# Connectors.net
KiCad netlist of a schematic drawn in Altium Designer
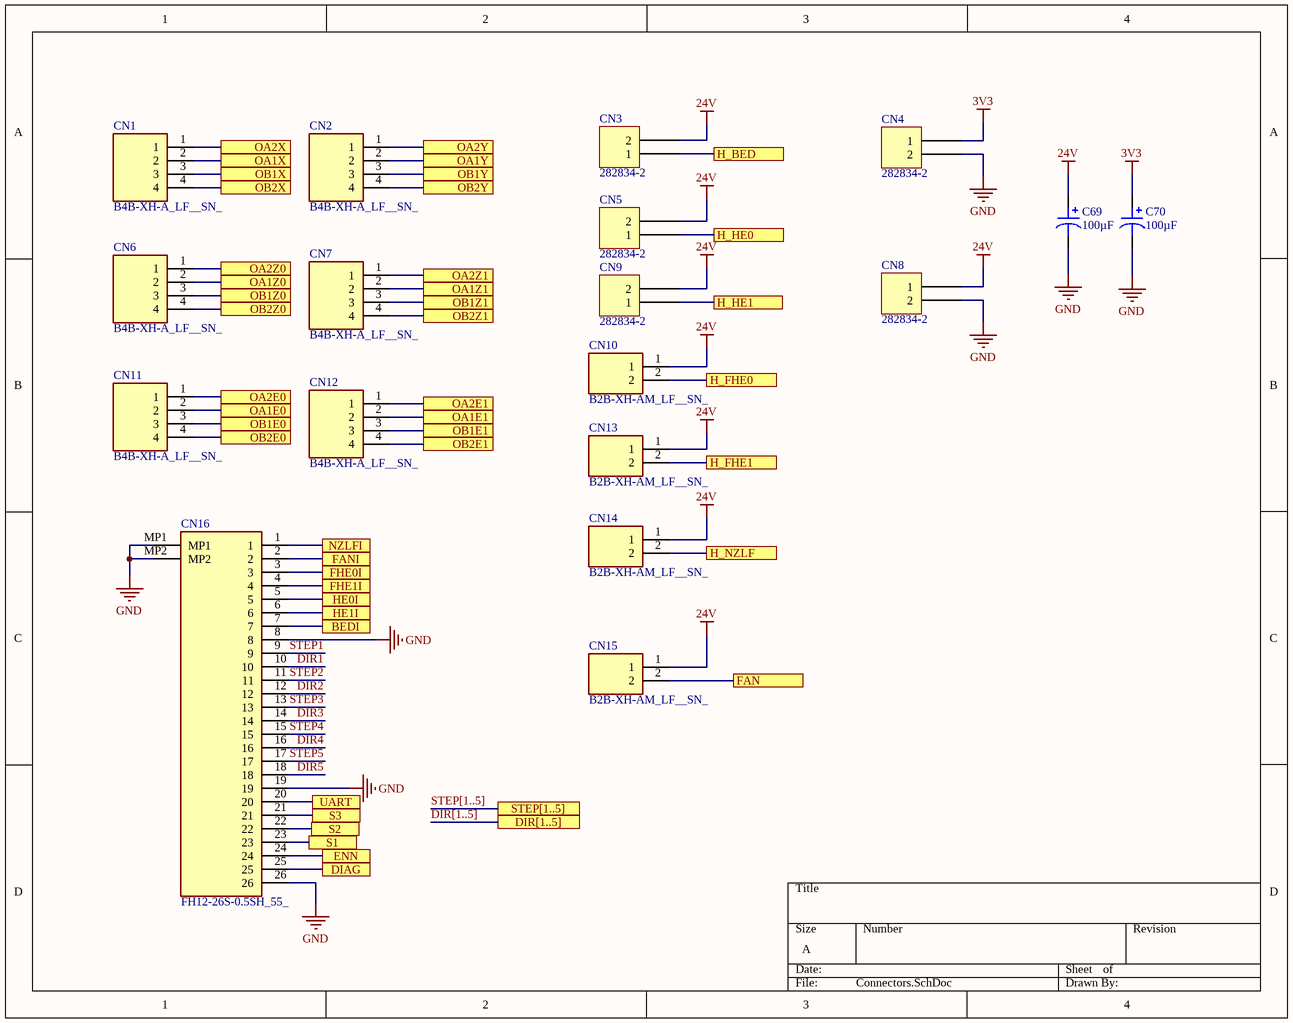
[diagram p0: Connectors.SchDoc]

(export (version "E")
  (design (tool "Eeschema 10.0.6"))
  (components
    (comp (ref "C69")
      (value "100µF")
      (footprint "CAP ALSMD POLY 5.3MM H6.0MM")
      (description "CAP ALUM POLY 100UF 20% 6.3V SMD")
      (fields
        (field (name "PART NUMBER") "6SVPC100M")
        (field (name "MANUFACTURER") "Panasonic Electronic Components")
      )
      (libsource (lib "Celestial Altium Library - altium_library") (part "Polarised Capacitor"))
    )
    (comp (ref "C70")
      (value "100µF")
      (footprint "CAP ALSMD POLY 5.3MM H6.0MM")
      (description "CAP ALUM POLY 100UF 20% 6.3V SMD")
      (fields
        (field (name "PART NUMBER") "6SVPC100M")
        (field (name "MANUFACTURER") "Panasonic Electronic Components")
      )
      (libsource (lib "Celestial Altium Library - altium_library") (part "Polarised Capacitor"))
    )
    (comp (ref "CN1")
      (value "B4B-XH-A_LF__SN_")
      (footprint "SamacSys:B4BXHALFSN")
      (description "Connector")
      (fields (field (name "MANUFACTURER_PART_NUMBER") "B4B-XH-A(LF)(SN)"))
      (libsource (lib "*") (part "B4B-XH-A_LF__SN_"))
    )
    (comp (ref "CN2")
      (value "B4B-XH-A_LF__SN_")
      (footprint "SamacSys:B4BXHALFSN")
      (description "Connector")
      (fields (field (name "MANUFACTURER_PART_NUMBER") "B4B-XH-A(LF)(SN)"))
      (libsource (lib "*") (part "B4B-XH-A_LF__SN_"))
    )
    (comp (ref "CN3")
      (value "282834-2")
      (footprint "TE 282834-2")
      (description "TERM BLK 2P SIDE ENT 2.54MM PCB")
      (fields (field (name "MANUFACTURER") "TE Connectivity AMP Connectors") (field (name "VOLTAGE") "150V"))
      (libsource (lib "Celestial Altium Library - altium_library") (part "2 Pin"))
    )
    (comp (ref "CN4")
      (value "282834-2")
      (footprint "TE 282834-2")
      (description "TERM BLK 2P SIDE ENT 2.54MM PCB")
      (fields (field (name "MANUFACTURER") "TE Connectivity AMP Connectors") (field (name "VOLTAGE") "150V"))
      (libsource (lib "") (part "2 Pin_1"))
    )
    (comp (ref "CN5")
      (value "282834-2")
      (footprint "TE 282834-2")
      (description "TERM BLK 2P SIDE ENT 2.54MM PCB")
      (fields (field (name "MANUFACTURER") "TE Connectivity AMP Connectors") (field (name "VOLTAGE") "150V"))
      (libsource (lib "Celestial Altium Library - altium_library") (part "2 Pin"))
    )
    (comp (ref "CN6")
      (value "B4B-XH-A_LF__SN_")
      (footprint "SamacSys:B4BXHALFSN")
      (description "Connector")
      (fields (field (name "MANUFACTURER_PART_NUMBER") "B4B-XH-A(LF)(SN)"))
      (libsource (lib "*") (part "B4B-XH-A_LF__SN_"))
    )
    (comp (ref "CN7")
      (value "B4B-XH-A_LF__SN_")
      (footprint "SamacSys:B4BXHALFSN")
      (description "Connector")
      (fields (field (name "MANUFACTURER_PART_NUMBER") "B4B-XH-A(LF)(SN)"))
      (libsource (lib "*") (part "B4B-XH-A_LF__SN_"))
    )
    (comp (ref "CN8")
      (value "282834-2")
      (footprint "TE 282834-2")
      (description "TERM BLK 2P SIDE ENT 2.54MM PCB")
      (fields (field (name "MANUFACTURER") "TE Connectivity AMP Connectors") (field (name "VOLTAGE") "150V"))
      (libsource (lib "") (part "2 Pin_1"))
    )
    (comp (ref "CN9")
      (value "282834-2")
      (footprint "TE 282834-2")
      (description "TERM BLK 2P SIDE ENT 2.54MM PCB")
      (fields (field (name "MANUFACTURER") "TE Connectivity AMP Connectors") (field (name "VOLTAGE") "150V"))
      (libsource (lib "Celestial Altium Library - altium_library") (part "2 Pin"))
    )
    (comp (ref "CN10")
      (value "B2B-XH-AM_LF__SN_")
      (footprint "SamacSys:B2BXHAMLFSN")
      (description "Connector")
      (fields (field (name "MANUFACTURER_PART_NUMBER") "B2B-XH-AM(LF)(SN)"))
      (libsource (lib "*") (part "B2B-XH-AM_LF__SN_"))
    )
    (comp (ref "CN11")
      (value "B4B-XH-A_LF__SN_")
      (footprint "SamacSys:B4BXHALFSN")
      (description "Connector")
      (fields (field (name "MANUFACTURER_PART_NUMBER") "B4B-XH-A(LF)(SN)"))
      (libsource (lib "*") (part "B4B-XH-A_LF__SN_"))
    )
    (comp (ref "CN12")
      (value "B4B-XH-A_LF__SN_")
      (footprint "SamacSys:B4BXHALFSN")
      (description "Connector")
      (fields (field (name "MANUFACTURER_PART_NUMBER") "B4B-XH-A(LF)(SN)"))
      (libsource (lib "*") (part "B4B-XH-A_LF__SN_"))
    )
    (comp (ref "CN13")
      (value "B2B-XH-AM_LF__SN_")
      (footprint "SamacSys:B2BXHAMLFSN")
      (description "Connector")
      (fields (field (name "MANUFACTURER_PART_NUMBER") "B2B-XH-AM(LF)(SN)"))
      (libsource (lib "*") (part "B2B-XH-AM_LF__SN_"))
    )
    (comp (ref "CN14")
      (value "B2B-XH-AM_LF__SN_")
      (footprint "SamacSys:B2BXHAMLFSN")
      (description "Connector")
      (fields (field (name "MANUFACTURER_PART_NUMBER") "B2B-XH-AM(LF)(SN)"))
      (libsource (lib "*") (part "B2B-XH-AM_LF__SN_"))
    )
    (comp (ref "CN15")
      (value "B2B-XH-AM_LF__SN_")
      (footprint "SamacSys:B2BXHAMLFSN")
      (description "Connector")
      (fields (field (name "MANUFACTURER_PART_NUMBER") "B2B-XH-AM(LF)(SN)"))
      (libsource (lib "*") (part "B2B-XH-AM_LF__SN_"))
    )
    (comp (ref "CN16")
      (value "FH12-26S-0.5SH_55_")
      (footprint "SamacSys:FH1226S05SH55")
      (description "Connector")
      (fields
        (field (name "MANUFACTURER_PART_NUMBER") "FH12-26S-0.5SH(55)")
        (field (name "MOUSER PART NUMBER") "798-FH12-26S-0.5SH55")
      )
      (libsource (lib "SamacSys") (part "FH12-26S-0.5SH_55_"))
    )
  )
  (nets
    (net (code "1") (name "/BEDI") (class "Default")
      (node (ref "CN16") (pin "7") (pinfunction "7_7") (pintype "passive"))
    )
    (net (code "2") (name "/DIAG") (class "Default")
      (node (ref "CN16") (pin "25") (pinfunction "25_25") (pintype "passive"))
    )
    (net (code "3") (name "/DIR1") (class "Default")
      (node (ref "CN16") (pin "10") (pinfunction "10_10") (pintype "passive"))
    )
    (net (code "4") (name "/DIR2") (class "Default")
      (node (ref "CN16") (pin "12") (pinfunction "12_12") (pintype "passive"))
    )
    (net (code "5") (name "/DIR3") (class "Default")
      (node (ref "CN16") (pin "14") (pinfunction "14_14") (pintype "passive"))
    )
    (net (code "6") (name "/DIR4") (class "Default")
      (node (ref "CN16") (pin "16") (pinfunction "16_16") (pintype "passive"))
    )
    (net (code "7") (name "/DIR5") (class "Default")
      (node (ref "CN16") (pin "18") (pinfunction "18_18") (pintype "passive"))
    )
    (net (code "9") (name "/ENN") (class "Default")
      (node (ref "CN16") (pin "24") (pinfunction "24_24") (pintype "passive"))
    )
    (net (code "10") (name "/FAN") (class "Default")
      (node (ref "CN15") (pin "2") (pinfunction "2_2") (pintype "passive"))
    )
    (net (code "11") (name "/FANI") (class "Default")
      (node (ref "CN16") (pin "2") (pinfunction "2_2") (pintype "passive"))
    )
    (net (code "12") (name "/FHE0I") (class "Default")
      (node (ref "CN16") (pin "3") (pinfunction "3_3") (pintype "passive"))
    )
    (net (code "13") (name "/FHE1I") (class "Default")
      (node (ref "CN16") (pin "4") (pinfunction "4_4") (pintype "passive"))
    )
    (net (code "14") (name "/HE0I") (class "Default")
      (node (ref "CN16") (pin "5") (pinfunction "5_5") (pintype "passive"))
    )
    (net (code "15") (name "/HE1I") (class "Default")
      (node (ref "CN16") (pin "6") (pinfunction "6_6") (pintype "passive"))
    )
    (net (code "16") (name "/H_BED") (class "Default")
      (node (ref "CN3") (pin "1") (pinfunction "1_1") (pintype "passive"))
    )
    (net (code "17") (name "/H_FHE0") (class "Default")
      (node (ref "CN10") (pin "2") (pinfunction "2_2") (pintype "passive"))
    )
    (net (code "18") (name "/H_FHE1") (class "Default")
      (node (ref "CN13") (pin "2") (pinfunction "2_2") (pintype "passive"))
    )
    (net (code "19") (name "/H_HE0") (class "Default")
      (node (ref "CN5") (pin "1") (pinfunction "1_1") (pintype "passive"))
    )
    (net (code "20") (name "/H_HE1") (class "Default")
      (node (ref "CN9") (pin "1") (pinfunction "1_1") (pintype "passive"))
    )
    (net (code "21") (name "/H_NZLF") (class "Default")
      (node (ref "CN14") (pin "2") (pinfunction "2_2") (pintype "passive"))
    )
    (net (code "22") (name "/NZLFI") (class "Default")
      (node (ref "CN16") (pin "1") (pinfunction "1_1") (pintype "passive"))
    )
    (net (code "23") (name "/OA1E0") (class "Default")
      (node (ref "CN11") (pin "2") (pinfunction "2_2") (pintype "passive"))
    )
    (net (code "24") (name "/OA1E1") (class "Default")
      (node (ref "CN12") (pin "2") (pinfunction "2_2") (pintype "passive"))
    )
    (net (code "25") (name "/OA1X") (class "Default")
      (node (ref "CN1") (pin "2") (pinfunction "2_2") (pintype "passive"))
    )
    (net (code "26") (name "/OA1Y") (class "Default")
      (node (ref "CN2") (pin "2") (pinfunction "2_2") (pintype "passive"))
    )
    (net (code "27") (name "/OA1Z0") (class "Default")
      (node (ref "CN6") (pin "2") (pinfunction "2_2") (pintype "passive"))
    )
    (net (code "28") (name "/OA1Z1") (class "Default")
      (node (ref "CN7") (pin "2") (pinfunction "2_2") (pintype "passive"))
    )
    (net (code "29") (name "/OA2E0") (class "Default")
      (node (ref "CN11") (pin "1") (pinfunction "1_1") (pintype "passive"))
    )
    (net (code "30") (name "/OA2E1") (class "Default")
      (node (ref "CN12") (pin "1") (pinfunction "1_1") (pintype "passive"))
    )
    (net (code "31") (name "/OA2X") (class "Default")
      (node (ref "CN1") (pin "1") (pinfunction "1_1") (pintype "passive"))
    )
    (net (code "32") (name "/OA2Y") (class "Default")
      (node (ref "CN2") (pin "1") (pinfunction "1_1") (pintype "passive"))
    )
    (net (code "33") (name "/OA2Z0") (class "Default")
      (node (ref "CN6") (pin "1") (pinfunction "1_1") (pintype "passive"))
    )
    (net (code "34") (name "/OA2Z1") (class "Default")
      (node (ref "CN7") (pin "1") (pinfunction "1_1") (pintype "passive"))
    )
    (net (code "35") (name "/OB1E0") (class "Default")
      (node (ref "CN11") (pin "3") (pinfunction "3_3") (pintype "passive"))
    )
    (net (code "36") (name "/OB1E1") (class "Default")
      (node (ref "CN12") (pin "3") (pinfunction "3_3") (pintype "passive"))
    )
    (net (code "37") (name "/OB1X") (class "Default")
      (node (ref "CN1") (pin "3") (pinfunction "3_3") (pintype "passive"))
    )
    (net (code "38") (name "/OB1Y") (class "Default")
      (node (ref "CN2") (pin "3") (pinfunction "3_3") (pintype "passive"))
    )
    (net (code "39") (name "/OB1Z0") (class "Default")
      (node (ref "CN6") (pin "3") (pinfunction "3_3") (pintype "passive"))
    )
    (net (code "40") (name "/OB1Z1") (class "Default")
      (node (ref "CN7") (pin "3") (pinfunction "3_3") (pintype "passive"))
    )
    (net (code "41") (name "/OB2E0") (class "Default")
      (node (ref "CN11") (pin "4") (pinfunction "4_4") (pintype "passive"))
    )
    (net (code "42") (name "/OB2E1") (class "Default")
      (node (ref "CN12") (pin "4") (pinfunction "4_4") (pintype "passive"))
    )
    (net (code "43") (name "/OB2X") (class "Default")
      (node (ref "CN1") (pin "4") (pinfunction "4_4") (pintype "passive"))
    )
    (net (code "44") (name "/OB2Y") (class "Default")
      (node (ref "CN2") (pin "4") (pinfunction "4_4") (pintype "passive"))
    )
    (net (code "45") (name "/OB2Z0") (class "Default")
      (node (ref "CN6") (pin "4") (pinfunction "4_4") (pintype "passive"))
    )
    (net (code "46") (name "/OB2Z1") (class "Default")
      (node (ref "CN7") (pin "4") (pinfunction "4_4") (pintype "passive"))
    )
    (net (code "47") (name "/S1") (class "Default")
      (node (ref "CN16") (pin "23") (pinfunction "23_23") (pintype "passive"))
    )
    (net (code "48") (name "/S2") (class "Default")
      (node (ref "CN16") (pin "22") (pinfunction "22_22") (pintype "passive"))
    )
    (net (code "49") (name "/S3") (class "Default")
      (node (ref "CN16") (pin "21") (pinfunction "21_21") (pintype "passive"))
    )
    (net (code "50") (name "/STEP1") (class "Default")
      (node (ref "CN16") (pin "9") (pinfunction "9_9") (pintype "passive"))
    )
    (net (code "51") (name "/STEP2") (class "Default")
      (node (ref "CN16") (pin "11") (pinfunction "11_11") (pintype "passive"))
    )
    (net (code "52") (name "/STEP3") (class "Default")
      (node (ref "CN16") (pin "13") (pinfunction "13_13") (pintype "passive"))
    )
    (net (code "53") (name "/STEP4") (class "Default")
      (node (ref "CN16") (pin "15") (pinfunction "15_15") (pintype "passive"))
    )
    (net (code "54") (name "/STEP5") (class "Default")
      (node (ref "CN16") (pin "17") (pinfunction "17_17") (pintype "passive"))
    )
    (net (code "56") (name "/UART") (class "Default")
      (node (ref "CN16") (pin "20") (pinfunction "20_20") (pintype "passive"))
    )
    (net (code "57") (name "3V3") (class "Default")
      (node (ref "C70") (pin "1") (pinfunction "1_1") (pintype "passive"))
      (node (ref "CN4") (pin "1") (pinfunction "1_1") (pintype "passive"))
    )
    (net (code "58") (name "24V") (class "Default")
      (node (ref "C69") (pin "1") (pinfunction "1_1") (pintype "passive"))
      (node (ref "CN10") (pin "1") (pinfunction "1_1") (pintype "passive"))
      (node (ref "CN13") (pin "1") (pinfunction "1_1") (pintype "passive"))
      (node (ref "CN14") (pin "1") (pinfunction "1_1") (pintype "passive"))
      (node (ref "CN15") (pin "1") (pinfunction "1_1") (pintype "passive"))
      (node (ref "CN3") (pin "2") (pinfunction "2_2") (pintype "passive"))
      (node (ref "CN5") (pin "2") (pinfunction "2_2") (pintype "passive"))
      (node (ref "CN8") (pin "1") (pinfunction "1_1") (pintype "passive"))
      (node (ref "CN9") (pin "2") (pinfunction "2_2") (pintype "passive"))
    )
    (net (code "59") (name "GND") (class "Default")
      (node (ref "C69") (pin "2") (pinfunction "2_2") (pintype "passive"))
      (node (ref "C70") (pin "2") (pinfunction "2_2") (pintype "passive"))
      (node (ref "CN16") (pin "19") (pinfunction "19_19") (pintype "passive"))
      (node (ref "CN16") (pin "26") (pinfunction "26_26") (pintype "passive"))
      (node (ref "CN16") (pin "8") (pinfunction "8_8") (pintype "passive"))
      (node (ref "CN16") (pin "MP1") (pinfunction "MP1_MP1") (pintype "passive"))
      (node (ref "CN16") (pin "MP2") (pinfunction "MP2_MP2") (pintype "passive"))
      (node (ref "CN4") (pin "2") (pinfunction "2_2") (pintype "passive"))
      (node (ref "CN8") (pin "2") (pinfunction "2_2") (pintype "passive"))
    )
  )
)
